# Beta22_SMD.net
KiCad netlist of a schematic drawn in EAGLE
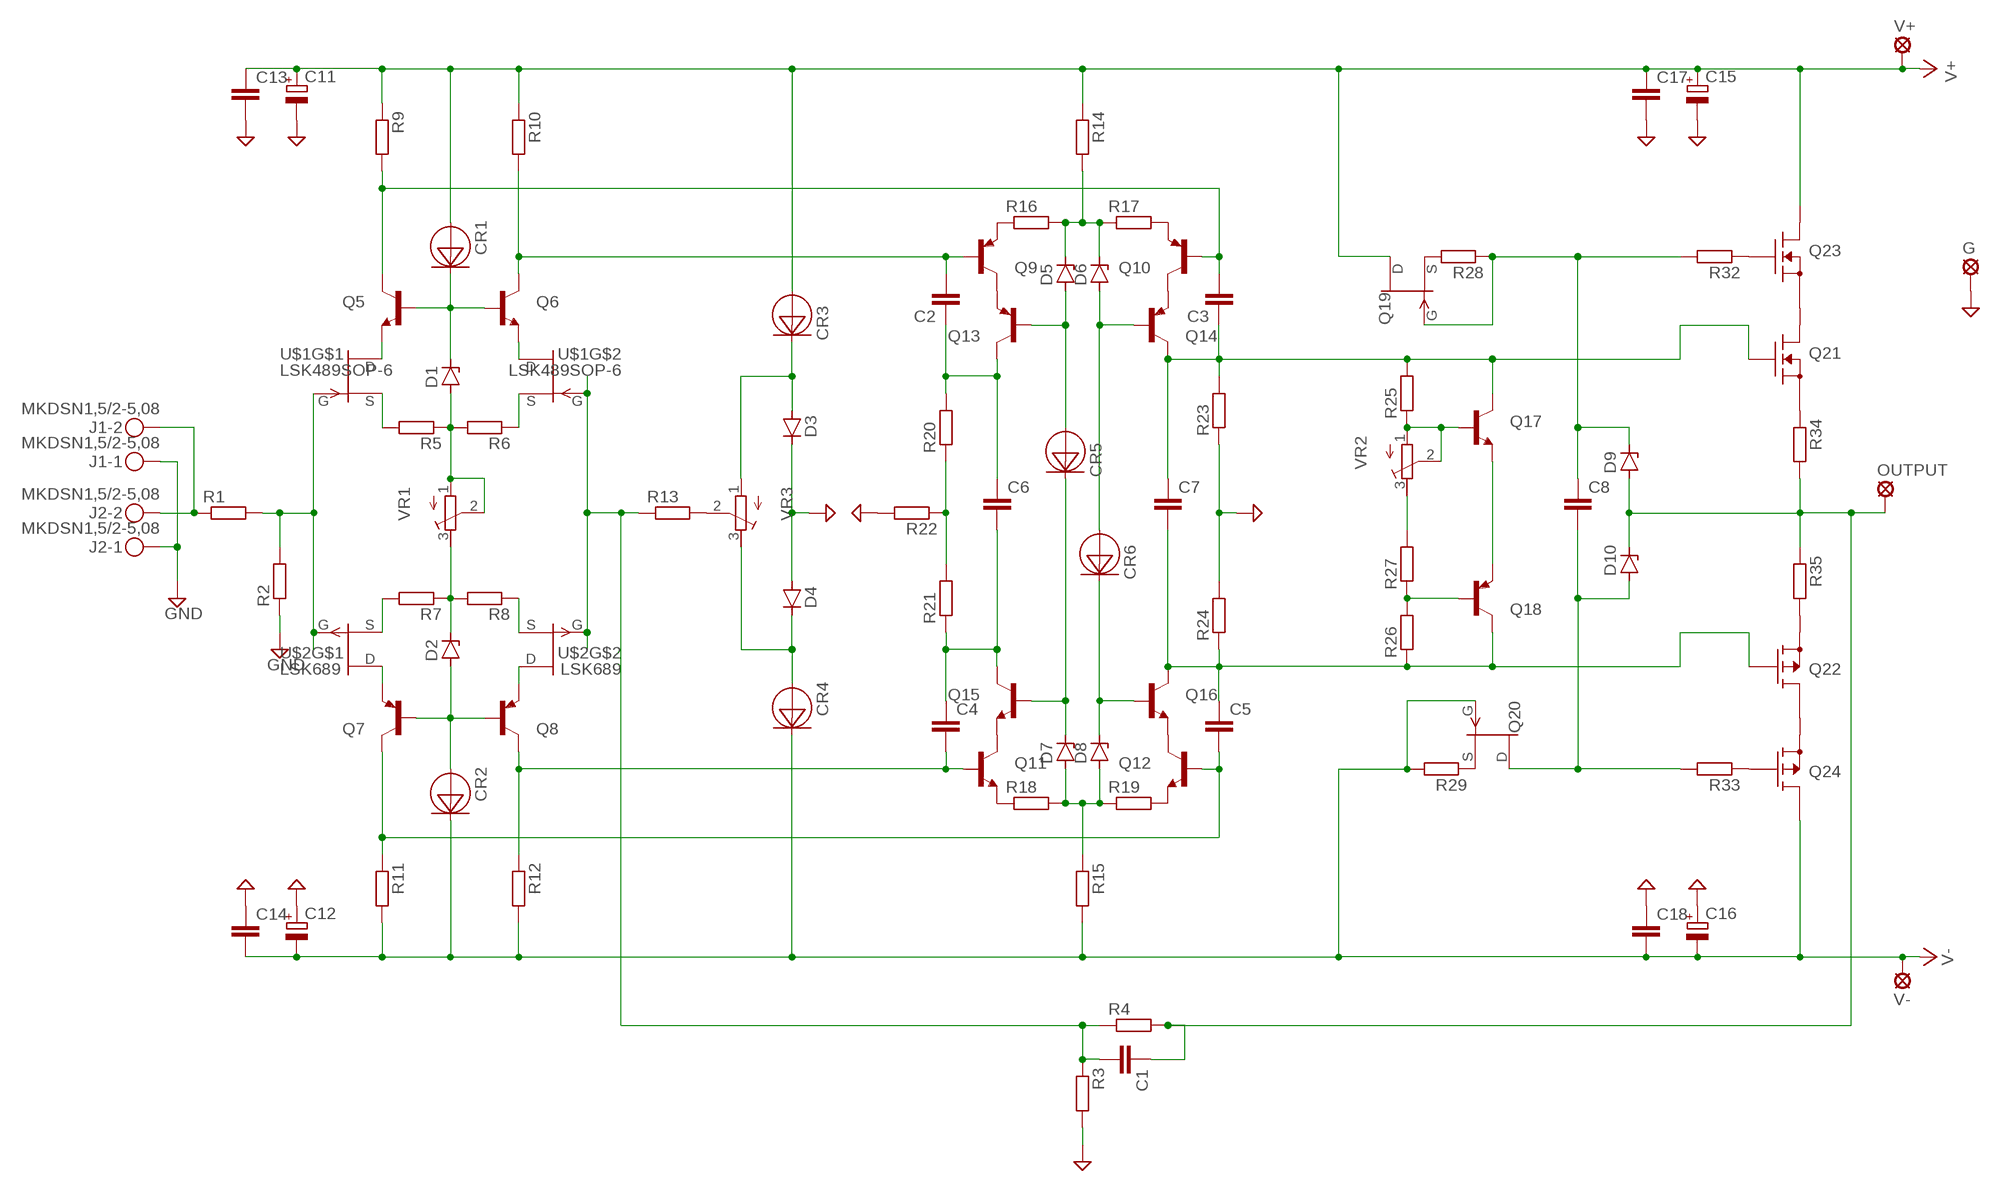
[diagram p0: schematic, sheet 1]

(export (version "E")
  (design (tool "Eeschema 10.0.6"))
  (components
    (comp (ref "C1")
      (value "C-EUC0805")
      (footprint "eagle-import:C0805")
      (libsource (lib "eagle-import") (part "C-EUC0805"))
    )
    (comp (ref "C2")
      (value "C-EUC0805")
      (footprint "eagle-import:C0805")
      (libsource (lib "eagle-import") (part "C-EUC0805"))
    )
    (comp (ref "C3")
      (value "C-EUC0805")
      (footprint "eagle-import:C0805")
      (libsource (lib "eagle-import") (part "C-EUC0805"))
    )
    (comp (ref "C4")
      (value "C-EUC0805")
      (footprint "eagle-import:C0805")
      (libsource (lib "eagle-import") (part "C-EUC0805"))
    )
    (comp (ref "C5")
      (value "C-EUC0805")
      (footprint "eagle-import:C0805")
      (libsource (lib "eagle-import") (part "C-EUC0805"))
    )
    (comp (ref "C6")
      (value "C-EUC0805")
      (footprint "eagle-import:C0805")
      (libsource (lib "eagle-import") (part "C-EUC0805"))
    )
    (comp (ref "C7")
      (value "C-EUC0805")
      (footprint "eagle-import:C0805")
      (libsource (lib "eagle-import") (part "C-EUC0805"))
    )
    (comp (ref "C8")
      (value "C-EUC0805")
      (footprint "eagle-import:C0805")
      (libsource (lib "eagle-import") (part "C-EUC0805"))
    )
    (comp (ref "C11")
      (value "CPOL-EUE5-13")
      (footprint "eagle-import:E5-13")
      (libsource (lib "eagle-import") (part "CPOL-EUE5-13"))
    )
    (comp (ref "C12")
      (value "CPOL-EUE5-13")
      (footprint "eagle-import:E5-13")
      (libsource (lib "eagle-import") (part "CPOL-EUE5-13"))
    )
    (comp (ref "C13")
      (value "C-EU050-055X075")
      (footprint "eagle-import:C050-055X075")
      (libsource (lib "eagle-import") (part "C-EU050-055X075"))
    )
    (comp (ref "C14")
      (value "C-EU050-055X075")
      (footprint "eagle-import:C050-055X075")
      (libsource (lib "eagle-import") (part "C-EU050-055X075"))
    )
    (comp (ref "C15")
      (value "CPOL-EUE7.5-18")
      (footprint "eagle-import:E7,5-18")
      (libsource (lib "eagle-import") (part "CPOL-EUE7.5-18"))
    )
    (comp (ref "C16")
      (value "CPOL-EUE7.5-18")
      (footprint "eagle-import:E7,5-18")
      (libsource (lib "eagle-import") (part "CPOL-EUE7.5-18"))
    )
    (comp (ref "C17")
      (value "C-EU050-055X075")
      (footprint "eagle-import:C050-055X075")
      (libsource (lib "eagle-import") (part "C-EU050-055X075"))
    )
    (comp (ref "C18")
      (value "C-EU050-055X075")
      (footprint "eagle-import:C050-055X075")
      (libsource (lib "eagle-import") (part "C-EU050-055X075"))
    )
    (comp (ref "CR1")
      (value "1N5283")
      (footprint "eagle-import:SMD")
      (libsource (lib "eagle-import") (part "1N5283"))
    )
    (comp (ref "CR2")
      (value "1N5283")
      (footprint "eagle-import:SMD")
      (libsource (lib "eagle-import") (part "1N5283"))
    )
    (comp (ref "CR3")
      (value "1N5283")
      (footprint "eagle-import:SMD")
      (libsource (lib "eagle-import") (part "1N5283"))
    )
    (comp (ref "CR4")
      (value "1N5283")
      (footprint "eagle-import:SMD")
      (libsource (lib "eagle-import") (part "1N5283"))
    )
    (comp (ref "CR5")
      (value "1N5283")
      (footprint "eagle-import:SMD")
      (libsource (lib "eagle-import") (part "1N5283"))
    )
    (comp (ref "CR6")
      (value "1N5283")
      (footprint "eagle-import:SMD")
      (libsource (lib "eagle-import") (part "1N5283"))
    )
    (comp (ref "D1")
      (value "ZENER-DIODESOD80C")
      (footprint "eagle-import:SOD80C")
      (libsource (lib "eagle-import") (part "ZENER-DIODESOD80C"))
    )
    (comp (ref "D2")
      (value "ZENER-DIODESOD80C")
      (footprint "eagle-import:SOD80C")
      (libsource (lib "eagle-import") (part "ZENER-DIODESOD80C"))
    )
    (comp (ref "D3")
      (value "DIODE-SOD80C")
      (footprint "eagle-import:SOD80C")
      (libsource (lib "eagle-import") (part "DIODE-SOD80C"))
    )
    (comp (ref "D4")
      (value "DIODE-SOD80C")
      (footprint "eagle-import:SOD80C")
      (libsource (lib "eagle-import") (part "DIODE-SOD80C"))
    )
    (comp (ref "D5")
      (value "ZENER-DIODESOD80C")
      (footprint "eagle-import:SOD80C")
      (libsource (lib "eagle-import") (part "ZENER-DIODESOD80C"))
    )
    (comp (ref "D6")
      (value "ZENER-DIODESOD80C")
      (footprint "eagle-import:SOD80C")
      (libsource (lib "eagle-import") (part "ZENER-DIODESOD80C"))
    )
    (comp (ref "D7")
      (value "ZENER-DIODESOD80C")
      (footprint "eagle-import:SOD80C")
      (libsource (lib "eagle-import") (part "ZENER-DIODESOD80C"))
    )
    (comp (ref "D8")
      (value "ZENER-DIODESOD80C")
      (footprint "eagle-import:SOD80C")
      (libsource (lib "eagle-import") (part "ZENER-DIODESOD80C"))
    )
    (comp (ref "D9")
      (value "ZENER-DIODESOD80C")
      (footprint "eagle-import:SOD80C")
      (libsource (lib "eagle-import") (part "ZENER-DIODESOD80C"))
    )
    (comp (ref "D10")
      (value "ZENER-DIODESOD80C")
      (footprint "eagle-import:SOD80C")
      (libsource (lib "eagle-import") (part "ZENER-DIODESOD80C"))
    )
    (comp (ref "G")
      (value "SE14")
      (footprint "eagle-import:SE14")
      (libsource (lib "eagle-import") (part "SE14"))
    )
    (comp (ref "J1")
      (value "MKDSN1,5/2-5,08")
      (footprint "eagle-import:MKDSN1,5_2-5,08")
      (libsource (lib "eagle-import") (part "MKDSN1,5/2-5,08"))
    )
    (comp (ref "J2")
      (value "MKDSN1,5/2-5,08")
      (footprint "eagle-import:MKDSN1,5_2-5,08")
      (libsource (lib "eagle-import") (part "MKDSN1,5/2-5,08"))
    )
    (comp (ref "OUTPUT")
      (value "SE14")
      (footprint "eagle-import:SE14")
      (libsource (lib "eagle-import") (part "SE14"))
    )
    (comp (ref "Q5")
      (value "BC550C")
      (footprint "eagle-import:TO92-EBC")
      (libsource (lib "eagle-import") (part "BC550C"))
    )
    (comp (ref "Q6")
      (value "BC550C")
      (footprint "eagle-import:TO92-EBC")
      (libsource (lib "eagle-import") (part "BC550C"))
    )
    (comp (ref "Q7")
      (value "BC560")
      (footprint "eagle-import:TO92_1")
      (libsource (lib "eagle-import") (part "BC560"))
    )
    (comp (ref "Q8")
      (value "BC560")
      (footprint "eagle-import:TO92_1")
      (libsource (lib "eagle-import") (part "BC560"))
    )
    (comp (ref "Q9")
      (value "BC560")
      (footprint "eagle-import:TO92_1")
      (libsource (lib "eagle-import") (part "BC560"))
    )
    (comp (ref "Q10")
      (value "BC560")
      (footprint "eagle-import:TO92_1")
      (libsource (lib "eagle-import") (part "BC560"))
    )
    (comp (ref "Q11")
      (value "BC550C")
      (footprint "eagle-import:TO92-EBC")
      (libsource (lib "eagle-import") (part "BC550C"))
    )
    (comp (ref "Q12")
      (value "BC550C")
      (footprint "eagle-import:TO92-EBC")
      (libsource (lib "eagle-import") (part "BC550C"))
    )
    (comp (ref "Q13")
      (value "BC560")
      (footprint "eagle-import:TO92_1")
      (libsource (lib "eagle-import") (part "BC560"))
    )
    (comp (ref "Q14")
      (value "BC560")
      (footprint "eagle-import:TO92_1")
      (libsource (lib "eagle-import") (part "BC560"))
    )
    (comp (ref "Q15")
      (value "BC550C")
      (footprint "eagle-import:TO92-EBC")
      (libsource (lib "eagle-import") (part "BC550C"))
    )
    (comp (ref "Q16")
      (value "BC550C")
      (footprint "eagle-import:TO92-EBC")
      (libsource (lib "eagle-import") (part "BC550C"))
    )
    (comp (ref "Q17")
      (value "BC550C")
      (footprint "eagle-import:TO92-EBC")
      (libsource (lib "eagle-import") (part "BC550C"))
    )
    (comp (ref "Q18")
      (value "BC560")
      (footprint "eagle-import:TO92_1")
      (libsource (lib "eagle-import") (part "BC560"))
    )
    (comp (ref "Q19")
      (value "SST5486")
      (footprint "eagle-import:SOT23")
      (libsource (lib "eagle-import") (part "?548SST6"))
    )
    (comp (ref "Q20")
      (value "SST5486")
      (footprint "eagle-import:SOT23")
      (libsource (lib "eagle-import") (part "?548SST6"))
    )
    (comp (ref "Q21")
      (value "IRFZ24N")
      (footprint "eagle-import:TO220V")
      (libsource (lib "eagle-import") (part "IRFZ24N"))
    )
    (comp (ref "Q22")
      (value "IRFZ34N")
      (footprint "eagle-import:TO220V")
      (libsource (lib "eagle-import") (part "IRFZ34N"))
    )
    (comp (ref "Q23")
      (value "IRFZ24N")
      (footprint "eagle-import:TO220V")
      (libsource (lib "eagle-import") (part "IRFZ24N"))
    )
    (comp (ref "Q24")
      (value "IRFZ34N")
      (footprint "eagle-import:TO220V")
      (libsource (lib "eagle-import") (part "IRFZ34N"))
    )
    (comp (ref "R1")
      (value "R-EU_MELF0204W")
      (footprint "eagle-import:MINI_MELF-0204W")
      (libsource (lib "eagle-import") (part "R-EU_MELF0204W"))
    )
    (comp (ref "R2")
      (value "R-EU_MELF0204W")
      (footprint "eagle-import:MINI_MELF-0204W")
      (libsource (lib "eagle-import") (part "R-EU_MELF0204W"))
    )
    (comp (ref "R3")
      (value "R-EU_MELF0204W")
      (footprint "eagle-import:MINI_MELF-0204W")
      (libsource (lib "eagle-import") (part "R-EU_MELF0204W"))
    )
    (comp (ref "R4")
      (value "R-EU_MELF0204W")
      (footprint "eagle-import:MINI_MELF-0204W")
      (libsource (lib "eagle-import") (part "R-EU_MELF0204W"))
    )
    (comp (ref "R5")
      (value "R-EU_MELF0204W")
      (footprint "eagle-import:MINI_MELF-0204W")
      (libsource (lib "eagle-import") (part "R-EU_MELF0204W"))
    )
    (comp (ref "R6")
      (value "R-EU_MELF0204W")
      (footprint "eagle-import:MINI_MELF-0204W")
      (libsource (lib "eagle-import") (part "R-EU_MELF0204W"))
    )
    (comp (ref "R7")
      (value "R-EU_MELF0204W")
      (footprint "eagle-import:MINI_MELF-0204W")
      (libsource (lib "eagle-import") (part "R-EU_MELF0204W"))
    )
    (comp (ref "R8")
      (value "R-EU_MELF0204W")
      (footprint "eagle-import:MINI_MELF-0204W")
      (libsource (lib "eagle-import") (part "R-EU_MELF0204W"))
    )
    (comp (ref "R9")
      (value "R-EU_MELF0204W")
      (footprint "eagle-import:MINI_MELF-0204W")
      (libsource (lib "eagle-import") (part "R-EU_MELF0204W"))
    )
    (comp (ref "R10")
      (value "R-EU_MELF0204W")
      (footprint "eagle-import:MINI_MELF-0204W")
      (libsource (lib "eagle-import") (part "R-EU_MELF0204W"))
    )
    (comp (ref "R11")
      (value "R-EU_MELF0204W")
      (footprint "eagle-import:MINI_MELF-0204W")
      (libsource (lib "eagle-import") (part "R-EU_MELF0204W"))
    )
    (comp (ref "R12")
      (value "R-EU_MELF0204W")
      (footprint "eagle-import:MINI_MELF-0204W")
      (libsource (lib "eagle-import") (part "R-EU_MELF0204W"))
    )
    (comp (ref "R13")
      (value "R-EU_MELF0204W")
      (footprint "eagle-import:MINI_MELF-0204W")
      (libsource (lib "eagle-import") (part "R-EU_MELF0204W"))
    )
    (comp (ref "R14")
      (value "R-EU_MELF0204W")
      (footprint "eagle-import:MINI_MELF-0204W")
      (libsource (lib "eagle-import") (part "R-EU_MELF0204W"))
    )
    (comp (ref "R15")
      (value "R-EU_MELF0204W")
      (footprint "eagle-import:MINI_MELF-0204W")
      (libsource (lib "eagle-import") (part "R-EU_MELF0204W"))
    )
    (comp (ref "R16")
      (value "R-EU_MELF0204W")
      (footprint "eagle-import:MINI_MELF-0204W")
      (libsource (lib "eagle-import") (part "R-EU_MELF0204W"))
    )
    (comp (ref "R17")
      (value "R-EU_MELF0204W")
      (footprint "eagle-import:MINI_MELF-0204W")
      (libsource (lib "eagle-import") (part "R-EU_MELF0204W"))
    )
    (comp (ref "R18")
      (value "R-EU_MELF0204W")
      (footprint "eagle-import:MINI_MELF-0204W")
      (libsource (lib "eagle-import") (part "R-EU_MELF0204W"))
    )
    (comp (ref "R19")
      (value "R-EU_MELF0204W")
      (footprint "eagle-import:MINI_MELF-0204W")
      (libsource (lib "eagle-import") (part "R-EU_MELF0204W"))
    )
    (comp (ref "R20")
      (value "R-EU_MELF0204W")
      (footprint "eagle-import:MINI_MELF-0204W")
      (libsource (lib "eagle-import") (part "R-EU_MELF0204W"))
    )
    (comp (ref "R21")
      (value "R-EU_MELF0204W")
      (footprint "eagle-import:MINI_MELF-0204W")
      (libsource (lib "eagle-import") (part "R-EU_MELF0204W"))
    )
    (comp (ref "R22")
      (value "R-EU_MELF0204W")
      (footprint "eagle-import:MINI_MELF-0204W")
      (libsource (lib "eagle-import") (part "R-EU_MELF0204W"))
    )
    (comp (ref "R23")
      (value "R-EU_MELF0204W")
      (footprint "eagle-import:MINI_MELF-0204W")
      (libsource (lib "eagle-import") (part "R-EU_MELF0204W"))
    )
    (comp (ref "R24")
      (value "R-EU_MELF0204W")
      (footprint "eagle-import:MINI_MELF-0204W")
      (libsource (lib "eagle-import") (part "R-EU_MELF0204W"))
    )
    (comp (ref "R25")
      (value "R-EU_MELF0204W")
      (footprint "eagle-import:MINI_MELF-0204W")
      (libsource (lib "eagle-import") (part "R-EU_MELF0204W"))
    )
    (comp (ref "R26")
      (value "R-EU_MELF0204W")
      (footprint "eagle-import:MINI_MELF-0204W")
      (libsource (lib "eagle-import") (part "R-EU_MELF0204W"))
    )
    (comp (ref "R27")
      (value "R-EU_MELF0204W")
      (footprint "eagle-import:MINI_MELF-0204W")
      (libsource (lib "eagle-import") (part "R-EU_MELF0204W"))
    )
    (comp (ref "R28")
      (value "R-EU_MELF0204W")
      (footprint "eagle-import:MINI_MELF-0204W")
      (libsource (lib "eagle-import") (part "R-EU_MELF0204W"))
    )
    (comp (ref "R29")
      (value "R-EU_MELF0204W")
      (footprint "eagle-import:MINI_MELF-0204W")
      (libsource (lib "eagle-import") (part "R-EU_MELF0204W"))
    )
    (comp (ref "R32")
      (value "R-EU_MELF0204W")
      (footprint "eagle-import:MINI_MELF-0204W")
      (libsource (lib "eagle-import") (part "R-EU_MELF0204W"))
    )
    (comp (ref "R33")
      (value "R-EU_MELF0204W")
      (footprint "eagle-import:MINI_MELF-0204W")
      (libsource (lib "eagle-import") (part "R-EU_MELF0204W"))
    )
    (comp (ref "R34")
      (value "R-EU_0617/17")
      (footprint "eagle-import:0617_17")
      (libsource (lib "eagle-import") (part "R-EU_0617/17"))
    )
    (comp (ref "R35")
      (value "R-EU_0617/17")
      (footprint "eagle-import:0617_17")
      (libsource (lib "eagle-import") (part "R-EU_0617/17"))
    )
    (comp (ref "U$1")
      (value "LSK489SOP-6")
      (footprint "eagle-import:SOT-23-6")
      (libsource (lib "eagle-import") (part "LSK489SOP-6"))
    )
    (comp (ref "U$2")
      (value "LSK689")
      (footprint "eagle-import:SOT-23-6")
      (libsource (lib "eagle-import") (part "LSK689"))
    )
    (comp (ref "V+")
      (value "SE14")
      (footprint "eagle-import:SE14")
      (libsource (lib "eagle-import") (part "SE14"))
    )
    (comp (ref "V-")
      (value "SE14")
      (footprint "eagle-import:SE14")
      (libsource (lib "eagle-import") (part "SE14"))
    )
    (comp (ref "VR1")
      (value "R-TRIMM3296W")
      (footprint "eagle-import:RTRIM3296W")
      (libsource (lib "eagle-import") (part "R-TRIMM3296W"))
    )
    (comp (ref "VR2")
      (value "R-TRIMM3296W")
      (footprint "eagle-import:RTRIM3296W")
      (libsource (lib "eagle-import") (part "R-TRIMM3296W"))
    )
    (comp (ref "VR3")
      (value "R-TRIMM3296W")
      (footprint "eagle-import:RTRIM3296W")
      (libsource (lib "eagle-import") (part "R-TRIMM3296W"))
    )
  )
  (nets
    (net (code "1") (name "GND") (class "Default")
      (node (ref "C11") (pin "-") (pinfunction "-_-") (pintype "passive"))
      (node (ref "C12") (pin "+") (pinfunction "+_+") (pintype "passive"))
      (node (ref "C13") (pin "2") (pinfunction "2_2") (pintype "passive"))
      (node (ref "C14") (pin "1") (pinfunction "1_1") (pintype "passive"))
      (node (ref "C15") (pin "-") (pinfunction "-_-") (pintype "passive"))
      (node (ref "C16") (pin "+") (pinfunction "+_+") (pintype "passive"))
      (node (ref "C17") (pin "2") (pinfunction "2_2") (pintype "passive"))
      (node (ref "C18") (pin "1") (pinfunction "1_1") (pintype "passive"))
      (node (ref "D3") (pin "C") (pinfunction "C_C") (pintype "passive"))
      (node (ref "D4") (pin "A") (pinfunction "A_A") (pintype "passive"))
      (node (ref "G") (pin "MP") (pinfunction "MP_MP") (pintype "passive"))
      (node (ref "J1") (pin "1") (pinfunction "KL_1") (pintype "passive"))
      (node (ref "J2") (pin "1") (pinfunction "KL_1") (pintype "passive"))
      (node (ref "R2") (pin "1") (pinfunction "1_1") (pintype "passive"))
      (node (ref "R22") (pin "2") (pinfunction "2_2") (pintype "passive"))
      (node (ref "R23") (pin "1") (pinfunction "1_1") (pintype "passive"))
      (node (ref "R24") (pin "2") (pinfunction "2_2") (pintype "passive"))
      (node (ref "R3") (pin "2") (pinfunction "2_2") (pintype "passive"))
    )
    (net (code "2") (name "Net-(C1-Pad1)") (class "Default")
      (node (ref "C1") (pin "1") (pinfunction "1_1") (pintype "passive"))
      (node (ref "D10") (pin "C") (pinfunction "C_C") (pintype "passive"))
      (node (ref "D9") (pin "A") (pinfunction "A_A") (pintype "passive"))
      (node (ref "OUTPUT") (pin "MP") (pinfunction "MP_MP") (pintype "passive"))
      (node (ref "R34") (pin "2") (pinfunction "2_2") (pintype "passive"))
      (node (ref "R35") (pin "1") (pinfunction "1_1") (pintype "passive"))
      (node (ref "R4") (pin "2") (pinfunction "2_2") (pintype "passive"))
    )
    (net (code "3") (name "Net-(C4-Pad1)") (class "Default")
      (node (ref "C4") (pin "1") (pinfunction "1_1") (pintype "passive"))
      (node (ref "C6") (pin "2") (pinfunction "2_2") (pintype "passive"))
      (node (ref "Q15") (pin "C") (pinfunction "C_C") (pintype "passive"))
      (node (ref "R21") (pin "1") (pinfunction "1_1") (pintype "passive"))
    )
    (net (code "4") (name "Net-(CR1-PadCATHODE)") (class "Default")
      (node (ref "CR1") (pin "CATHODE") (pinfunction "CATHODE_CATHODE") (pintype "passive"))
      (node (ref "D1") (pin "C") (pinfunction "C_C") (pintype "passive"))
      (node (ref "Q5") (pin "B") (pinfunction "B_B") (pintype "passive"))
      (node (ref "Q6") (pin "B") (pinfunction "B_B") (pintype "passive"))
    )
    (net (code "5") (name "Net-(CR5-PadCATHODE)") (class "Default")
      (node (ref "CR5") (pin "CATHODE") (pinfunction "CATHODE_CATHODE") (pintype "passive"))
      (node (ref "D7") (pin "C") (pinfunction "C_C") (pintype "passive"))
      (node (ref "Q15") (pin "B") (pinfunction "B_B") (pintype "passive"))
    )
    (net (code "6") (name "Net-(CR6-PadCATHODE)") (class "Default")
      (node (ref "CR6") (pin "CATHODE") (pinfunction "CATHODE_CATHODE") (pintype "passive"))
      (node (ref "D8") (pin "C") (pinfunction "C_C") (pintype "passive"))
      (node (ref "Q16") (pin "B") (pinfunction "B_B") (pintype "passive"))
    )
    (net (code "7") (name "Net-(D5-PadC)") (class "Default")
      (node (ref "D5") (pin "C") (pinfunction "C_C") (pintype "passive"))
      (node (ref "D6") (pin "C") (pinfunction "C_C") (pintype "passive"))
      (node (ref "R14") (pin "2") (pinfunction "2_2") (pintype "passive"))
      (node (ref "R16") (pin "2") (pinfunction "2_2") (pintype "passive"))
      (node (ref "R17") (pin "1") (pinfunction "1_1") (pintype "passive"))
    )
    (net (code "8") (name "Net-(D7-PadA)") (class "Default")
      (node (ref "D7") (pin "A") (pinfunction "A_A") (pintype "passive"))
      (node (ref "D8") (pin "A") (pinfunction "A_A") (pintype "passive"))
      (node (ref "R15") (pin "1") (pinfunction "1_1") (pintype "passive"))
      (node (ref "R18") (pin "2") (pinfunction "2_2") (pintype "passive"))
      (node (ref "R19") (pin "1") (pinfunction "1_1") (pintype "passive"))
    )
    (net (code "9") (name "Net-(J1B-KL)") (class "Default")
      (node (ref "J1") (pin "2") (pinfunction "KL_2") (pintype "passive"))
      (node (ref "J2") (pin "2") (pinfunction "KL_2") (pintype "passive"))
      (node (ref "R1") (pin "1") (pinfunction "1_1") (pintype "passive"))
    )
    (net (code "10") (name "Net-(Q7-B)") (class "Default")
      (node (ref "CR2") (pin "ANODE") (pinfunction "ANODE_ANODE") (pintype "passive"))
      (node (ref "D2") (pin "A") (pinfunction "A_A") (pintype "passive"))
      (node (ref "Q7") (pin "2") (pinfunction "B_2") (pintype "passive"))
      (node (ref "Q8") (pin "2") (pinfunction "B_2") (pintype "passive"))
    )
    (net (code "11") (name "Net-(Q7-C)") (class "Default")
      (node (ref "C5") (pin "2") (pinfunction "2_2") (pintype "passive"))
      (node (ref "Q12") (pin "B") (pinfunction "B_B") (pintype "passive"))
      (node (ref "Q7") (pin "1") (pinfunction "C_1") (pintype "passive"))
      (node (ref "R11") (pin "1") (pinfunction "1_1") (pintype "passive"))
    )
    (net (code "12") (name "Net-(Q7-E)") (class "Default")
      (node (ref "Q7") (pin "3") (pinfunction "E_3") (pintype "passive"))
      (node (ref "U$2") (pin "2") (pinfunction "D_2") (pintype "passive"))
    )
    (net (code "13") (name "Net-(Q8-C)") (class "Default")
      (node (ref "C4") (pin "2") (pinfunction "2_2") (pintype "passive"))
      (node (ref "Q11") (pin "B") (pinfunction "B_B") (pintype "passive"))
      (node (ref "Q8") (pin "1") (pinfunction "C_1") (pintype "passive"))
      (node (ref "R12") (pin "1") (pinfunction "1_1") (pintype "passive"))
    )
    (net (code "14") (name "Net-(Q8-E)") (class "Default")
      (node (ref "Q8") (pin "3") (pinfunction "E_3") (pintype "passive"))
      (node (ref "U$2") (pin "5") (pinfunction "D_5") (pintype "passive"))
    )
    (net (code "15") (name "Net-(Q9-B)") (class "Default")
      (node (ref "C2") (pin "2") (pinfunction "2_2") (pintype "passive"))
      (node (ref "Q6") (pin "C") (pinfunction "C_C") (pintype "passive"))
      (node (ref "Q9") (pin "2") (pinfunction "B_2") (pintype "passive"))
      (node (ref "R10") (pin "2") (pinfunction "2_2") (pintype "passive"))
    )
    (net (code "16") (name "Net-(Q9-E)") (class "Default")
      (node (ref "Q9") (pin "3") (pinfunction "E_3") (pintype "passive"))
      (node (ref "R16") (pin "1") (pinfunction "1_1") (pintype "passive"))
    )
    (net (code "17") (name "Net-(Q10-B)") (class "Default")
      (node (ref "C3") (pin "2") (pinfunction "2_2") (pintype "passive"))
      (node (ref "Q10") (pin "2") (pinfunction "B_2") (pintype "passive"))
      (node (ref "Q5") (pin "C") (pinfunction "C_C") (pintype "passive"))
      (node (ref "R9") (pin "2") (pinfunction "2_2") (pintype "passive"))
    )
    (net (code "18") (name "Net-(Q10-C)") (class "Default")
      (node (ref "Q10") (pin "1") (pinfunction "C_1") (pintype "passive"))
      (node (ref "Q14") (pin "3") (pinfunction "E_3") (pintype "passive"))
    )
    (net (code "19") (name "Net-(Q10-E)") (class "Default")
      (node (ref "Q10") (pin "3") (pinfunction "E_3") (pintype "passive"))
      (node (ref "R17") (pin "2") (pinfunction "2_2") (pintype "passive"))
    )
    (net (code "20") (name "Net-(Q11-PadC)") (class "Default")
      (node (ref "Q11") (pin "C") (pinfunction "C_C") (pintype "passive"))
      (node (ref "Q15") (pin "E") (pinfunction "E_E") (pintype "passive"))
    )
    (net (code "21") (name "Net-(Q11-PadE)") (class "Default")
      (node (ref "Q11") (pin "E") (pinfunction "E_E") (pintype "passive"))
      (node (ref "R18") (pin "1") (pinfunction "1_1") (pintype "passive"))
    )
    (net (code "22") (name "Net-(Q12-PadC)") (class "Default")
      (node (ref "Q12") (pin "C") (pinfunction "C_C") (pintype "passive"))
      (node (ref "Q16") (pin "E") (pinfunction "E_E") (pintype "passive"))
    )
    (net (code "23") (name "Net-(Q12-PadE)") (class "Default")
      (node (ref "Q12") (pin "E") (pinfunction "E_E") (pintype "passive"))
      (node (ref "R19") (pin "2") (pinfunction "2_2") (pintype "passive"))
    )
    (net (code "24") (name "Net-(Q13-B)") (class "Default")
      (node (ref "CR5") (pin "ANODE") (pinfunction "ANODE_ANODE") (pintype "passive"))
      (node (ref "D5") (pin "A") (pinfunction "A_A") (pintype "passive"))
      (node (ref "Q13") (pin "2") (pinfunction "B_2") (pintype "passive"))
    )
    (net (code "25") (name "Net-(Q13-C)") (class "Default")
      (node (ref "C2") (pin "1") (pinfunction "1_1") (pintype "passive"))
      (node (ref "C6") (pin "1") (pinfunction "1_1") (pintype "passive"))
      (node (ref "Q13") (pin "1") (pinfunction "C_1") (pintype "passive"))
      (node (ref "R20") (pin "2") (pinfunction "2_2") (pintype "passive"))
    )
    (net (code "26") (name "Net-(Q13-E)") (class "Default")
      (node (ref "Q13") (pin "3") (pinfunction "E_3") (pintype "passive"))
      (node (ref "Q9") (pin "1") (pinfunction "C_1") (pintype "passive"))
    )
    (net (code "27") (name "Net-(Q14-B)") (class "Default")
      (node (ref "CR6") (pin "ANODE") (pinfunction "ANODE_ANODE") (pintype "passive"))
      (node (ref "D6") (pin "A") (pinfunction "A_A") (pintype "passive"))
      (node (ref "Q14") (pin "2") (pinfunction "B_2") (pintype "passive"))
    )
    (net (code "28") (name "Net-(Q14-C)") (class "Default")
      (node (ref "C3") (pin "1") (pinfunction "1_1") (pintype "passive"))
      (node (ref "C7") (pin "1") (pinfunction "1_1") (pintype "passive"))
      (node (ref "Q14") (pin "1") (pinfunction "C_1") (pintype "passive"))
      (node (ref "Q17") (pin "C") (pinfunction "C_C") (pintype "passive"))
      (node (ref "Q21") (pin "1") (pinfunction "G_1") (pintype "passive"))
      (node (ref "R23") (pin "2") (pinfunction "2_2") (pintype "passive"))
      (node (ref "R25") (pin "2") (pinfunction "2_2") (pintype "passive"))
    )
    (net (code "29") (name "Net-(Q18-B)") (class "Default")
      (node (ref "Q18") (pin "2") (pinfunction "B_2") (pintype "passive"))
      (node (ref "R26") (pin "2") (pinfunction "2_2") (pintype "passive"))
      (node (ref "R27") (pin "1") (pinfunction "1_1") (pintype "passive"))
    )
    (net (code "30") (name "Net-(Q18-C)") (class "Default")
      (node (ref "C5") (pin "1") (pinfunction "1_1") (pintype "passive"))
      (node (ref "C7") (pin "2") (pinfunction "2_2") (pintype "passive"))
      (node (ref "Q16") (pin "C") (pinfunction "C_C") (pintype "passive"))
      (node (ref "Q18") (pin "1") (pinfunction "C_1") (pintype "passive"))
      (node (ref "Q22") (pin "1") (pinfunction "G_1") (pintype "passive"))
      (node (ref "R24") (pin "1") (pinfunction "1_1") (pintype "passive"))
      (node (ref "R26") (pin "1") (pinfunction "1_1") (pintype "passive"))
    )
    (net (code "31") (name "Net-(Q18-E)") (class "Default")
      (node (ref "Q17") (pin "E") (pinfunction "E_E") (pintype "passive"))
      (node (ref "Q18") (pin "3") (pinfunction "E_3") (pintype "passive"))
    )
    (net (code "32") (name "Net-(Q19-G)") (class "Default")
      (node (ref "C8") (pin "1") (pinfunction "1_1") (pintype "passive"))
      (node (ref "D9") (pin "C") (pinfunction "C_C") (pintype "passive"))
      (node (ref "Q19") (pin "3") (pinfunction "G_3") (pintype "passive"))
      (node (ref "R28") (pin "1") (pinfunction "1_1") (pintype "passive"))
      (node (ref "R32") (pin "2") (pinfunction "2_2") (pintype "passive"))
    )
    (net (code "33") (name "Net-(Q19-S)") (class "Default")
      (node (ref "Q19") (pin "2") (pinfunction "S_2") (pintype "passive"))
      (node (ref "R28") (pin "2") (pinfunction "2_2") (pintype "passive"))
    )
    (net (code "34") (name "Net-(Q20-D)") (class "Default")
      (node (ref "C8") (pin "2") (pinfunction "2_2") (pintype "passive"))
      (node (ref "D10") (pin "A") (pinfunction "A_A") (pintype "passive"))
      (node (ref "Q20") (pin "1") (pinfunction "D_1") (pintype "passive"))
      (node (ref "R33") (pin "2") (pinfunction "2_2") (pintype "passive"))
    )
    (net (code "35") (name "Net-(Q20-S)") (class "Default")
      (node (ref "Q20") (pin "2") (pinfunction "S_2") (pintype "passive"))
      (node (ref "R29") (pin "1") (pinfunction "1_1") (pintype "passive"))
    )
    (net (code "36") (name "Net-(Q21-D)") (class "Default")
      (node (ref "Q21") (pin "2") (pinfunction "D_2") (pintype "passive"))
      (node (ref "Q23") (pin "3") (pinfunction "S_3") (pintype "passive"))
    )
    (net (code "37") (name "Net-(Q21-S)") (class "Default")
      (node (ref "Q21") (pin "3") (pinfunction "S_3") (pintype "passive"))
      (node (ref "R34") (pin "1") (pinfunction "1_1") (pintype "passive"))
    )
    (net (code "38") (name "Net-(Q22-D)") (class "Default")
      (node (ref "Q22") (pin "2") (pinfunction "D_2") (pintype "passive"))
      (node (ref "Q24") (pin "3") (pinfunction "S_3") (pintype "passive"))
    )
    (net (code "39") (name "Net-(Q22-S)") (class "Default")
      (node (ref "Q22") (pin "3") (pinfunction "S_3") (pintype "passive"))
      (node (ref "R35") (pin "2") (pinfunction "2_2") (pintype "passive"))
    )
    (net (code "40") (name "Net-(Q23-G)") (class "Default")
      (node (ref "Q23") (pin "1") (pinfunction "G_1") (pintype "passive"))
      (node (ref "R32") (pin "1") (pinfunction "1_1") (pintype "passive"))
    )
    (net (code "41") (name "Net-(Q24-G)") (class "Default")
      (node (ref "Q24") (pin "1") (pinfunction "G_1") (pintype "passive"))
      (node (ref "R33") (pin "1") (pinfunction "1_1") (pintype "passive"))
    )
    (net (code "42") (name "Net-(R20-Pad1)") (class "Default")
      (node (ref "R20") (pin "1") (pinfunction "1_1") (pintype "passive"))
      (node (ref "R21") (pin "2") (pinfunction "2_2") (pintype "passive"))
      (node (ref "R22") (pin "1") (pinfunction "1_1") (pintype "passive"))
    )
    (net (code "43") (name "Net-(U$1A-D)") (class "Default")
      (node (ref "Q5") (pin "E") (pinfunction "E_E") (pintype "passive"))
      (node (ref "U$1") (pin "2") (pinfunction "D_2") (pintype "passive"))
    )
    (net (code "44") (name "Net-(U$1A-G)") (class "Default")
      (node (ref "R1") (pin "2") (pinfunction "2_2") (pintype "passive"))
      (node (ref "R2") (pin "2") (pinfunction "2_2") (pintype "passive"))
      (node (ref "U$1") (pin "1") (pinfunction "G_1") (pintype "passive"))
      (node (ref "U$2") (pin "1") (pinfunction "G_1") (pintype "passive"))
    )
    (net (code "45") (name "Net-(U$1A-S)") (class "Default")
      (node (ref "R5") (pin "2") (pinfunction "2_2") (pintype "passive"))
      (node (ref "U$1") (pin "3") (pinfunction "S_3") (pintype "passive"))
    )
    (net (code "46") (name "Net-(U$1B-D)") (class "Default")
      (node (ref "Q6") (pin "E") (pinfunction "E_E") (pintype "passive"))
      (node (ref "U$1") (pin "5") (pinfunction "D_5") (pintype "passive"))
    )
    (net (code "47") (name "Net-(U$1B-G)") (class "Default")
      (node (ref "C1") (pin "2") (pinfunction "2_2") (pintype "passive"))
      (node (ref "R13") (pin "1") (pinfunction "1_1") (pintype "passive"))
      (node (ref "R3") (pin "1") (pinfunction "1_1") (pintype "passive"))
      (node (ref "R4") (pin "1") (pinfunction "1_1") (pintype "passive"))
      (node (ref "U$1") (pin "4") (pinfunction "G_4") (pintype "passive"))
      (node (ref "U$2") (pin "4") (pinfunction "G_4") (pintype "passive"))
    )
    (net (code "48") (name "Net-(U$1B-S)") (class "Default")
      (node (ref "R6") (pin "1") (pinfunction "1_1") (pintype "passive"))
      (node (ref "U$1") (pin "6") (pinfunction "S_6") (pintype "passive"))
    )
    (net (code "49") (name "Net-(U$2A-S)") (class "Default")
      (node (ref "R7") (pin "2") (pinfunction "2_2") (pintype "passive"))
      (node (ref "U$2") (pin "3") (pinfunction "S_3") (pintype "passive"))
    )
    (net (code "50") (name "Net-(U$2B-S)") (class "Default")
      (node (ref "R8") (pin "1") (pinfunction "1_1") (pintype "passive"))
      (node (ref "U$2") (pin "6") (pinfunction "S_6") (pintype "passive"))
    )
    (net (code "51") (name "Net-(VR1-A)") (class "Default")
      (node (ref "D1") (pin "A") (pinfunction "A_A") (pintype "passive"))
      (node (ref "R5") (pin "1") (pinfunction "1_1") (pintype "passive"))
      (node (ref "R6") (pin "2") (pinfunction "2_2") (pintype "passive"))
      (node (ref "VR1") (pin "1") (pinfunction "A_1") (pintype "passive"))
      (node (ref "VR1") (pin "2") (pinfunction "S_2") (pintype "passive"))
    )
    (net (code "52") (name "Net-(VR1-E)") (class "Default")
      (node (ref "D2") (pin "C") (pinfunction "C_C") (pintype "passive"))
      (node (ref "R7") (pin "1") (pinfunction "1_1") (pintype "passive"))
      (node (ref "R8") (pin "2") (pinfunction "2_2") (pintype "passive"))
      (node (ref "VR1") (pin "3") (pinfunction "E_3") (pintype "passive"))
    )
    (net (code "53") (name "Net-(VR2-A)") (class "Default")
      (node (ref "Q17") (pin "B") (pinfunction "B_B") (pintype "passive"))
      (node (ref "R25") (pin "1") (pinfunction "1_1") (pintype "passive"))
      (node (ref "VR2") (pin "1") (pinfunction "A_1") (pintype "passive"))
      (node (ref "VR2") (pin "2") (pinfunction "S_2") (pintype "passive"))
    )
    (net (code "54") (name "Net-(VR2-E)") (class "Default")
      (node (ref "R27") (pin "2") (pinfunction "2_2") (pintype "passive"))
      (node (ref "VR2") (pin "3") (pinfunction "E_3") (pintype "passive"))
    )
    (net (code "55") (name "Net-(VR3-A)") (class "Default")
      (node (ref "CR3") (pin "CATHODE") (pinfunction "CATHODE_CATHODE") (pintype "passive"))
      (node (ref "D3") (pin "A") (pinfunction "A_A") (pintype "passive"))
      (node (ref "VR3") (pin "1") (pinfunction "A_1") (pintype "passive"))
    )
    (net (code "56") (name "Net-(VR3-E)") (class "Default")
      (node (ref "CR4") (pin "ANODE") (pinfunction "ANODE_ANODE") (pintype "passive"))
      (node (ref "D4") (pin "C") (pinfunction "C_C") (pintype "passive"))
      (node (ref "VR3") (pin "3") (pinfunction "E_3") (pintype "passive"))
    )
    (net (code "57") (name "Net-(VR3-S)") (class "Default")
      (node (ref "R13") (pin "2") (pinfunction "2_2") (pintype "passive"))
      (node (ref "VR3") (pin "2") (pinfunction "S_2") (pintype "passive"))
    )
    (net (code "58") (name "V+") (class "Default")
      (node (ref "C11") (pin "+") (pinfunction "+_+") (pintype "passive"))
      (node (ref "C13") (pin "1") (pinfunction "1_1") (pintype "passive"))
      (node (ref "C15") (pin "+") (pinfunction "+_+") (pintype "passive"))
      (node (ref "C17") (pin "1") (pinfunction "1_1") (pintype "passive"))
      (node (ref "CR1") (pin "ANODE") (pinfunction "ANODE_ANODE") (pintype "passive"))
      (node (ref "CR3") (pin "ANODE") (pinfunction "ANODE_ANODE") (pintype "passive"))
      (node (ref "Q19") (pin "1") (pinfunction "D_1") (pintype "passive"))
      (node (ref "Q23") (pin "2") (pinfunction "D_2") (pintype "passive"))
      (node (ref "R10") (pin "1") (pinfunction "1_1") (pintype "passive"))
      (node (ref "R14") (pin "1") (pinfunction "1_1") (pintype "passive"))
      (node (ref "R9") (pin "1") (pinfunction "1_1") (pintype "passive"))
      (node (ref "V+") (pin "MP") (pinfunction "MP_MP") (pintype "passive"))
    )
    (net (code "59") (name "V-") (class "Default")
      (node (ref "C12") (pin "-") (pinfunction "-_-") (pintype "passive"))
      (node (ref "C14") (pin "2") (pinfunction "2_2") (pintype "passive"))
      (node (ref "C16") (pin "-") (pinfunction "-_-") (pintype "passive"))
      (node (ref "C18") (pin "2") (pinfunction "2_2") (pintype "passive"))
      (node (ref "CR2") (pin "CATHODE") (pinfunction "CATHODE_CATHODE") (pintype "passive"))
      (node (ref "CR4") (pin "CATHODE") (pinfunction "CATHODE_CATHODE") (pintype "passive"))
      (node (ref "Q20") (pin "3") (pinfunction "G_3") (pintype "passive"))
      (node (ref "Q24") (pin "2") (pinfunction "D_2") (pintype "passive"))
      (node (ref "R11") (pin "2") (pinfunction "2_2") (pintype "passive"))
      (node (ref "R12") (pin "2") (pinfunction "2_2") (pintype "passive"))
      (node (ref "R15") (pin "2") (pinfunction "2_2") (pintype "passive"))
      (node (ref "R29") (pin "2") (pinfunction "2_2") (pintype "passive"))
      (node (ref "V-") (pin "MP") (pinfunction "MP_MP") (pintype "passive"))
    )
  )
)
